# Keg_Cop_-_Tallboy.net
KiCad netlist of a schematic drawn in EAGLE
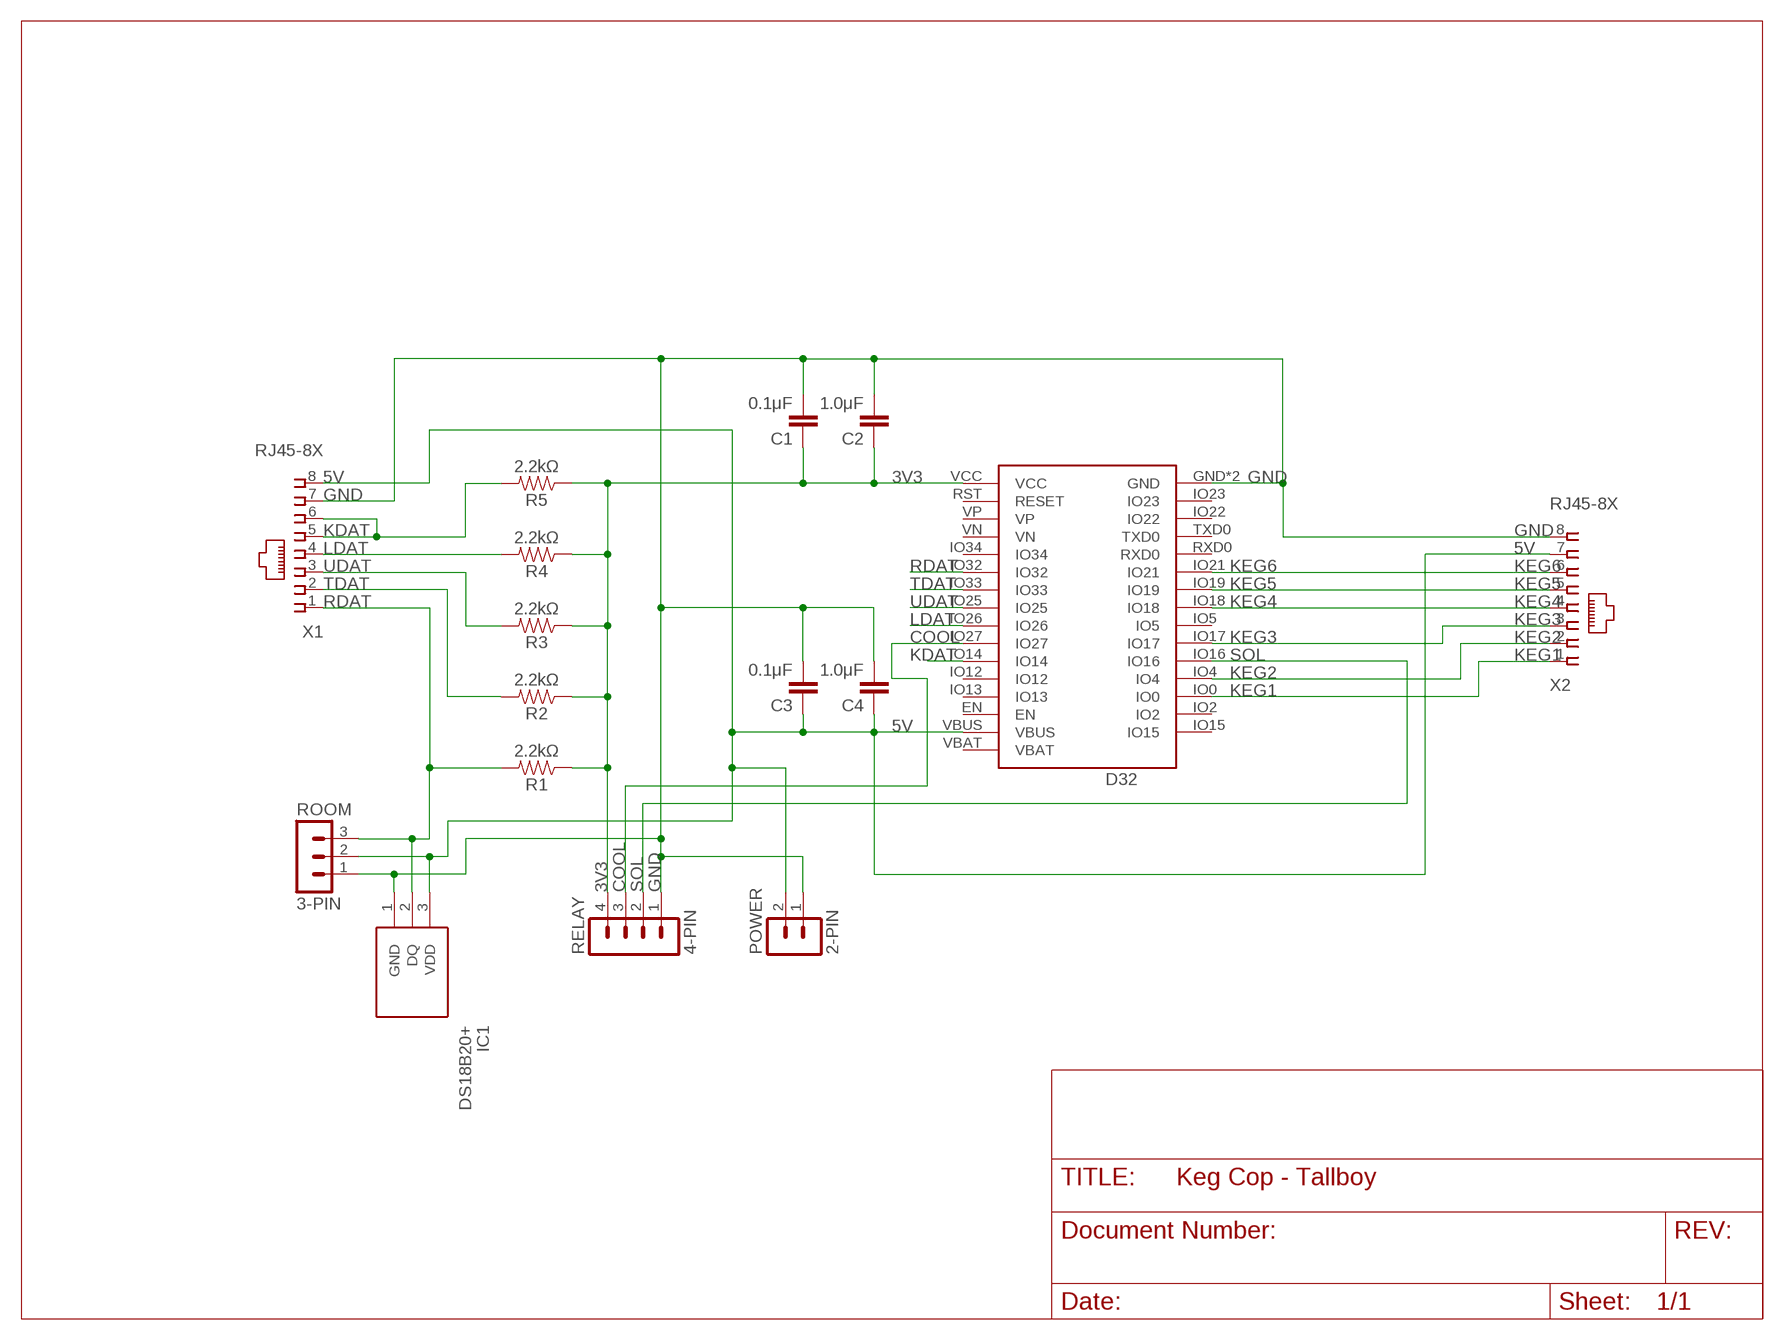
[diagram p0: schematic, sheet 1]

(export (version "E")
  (design (tool "Eeschema 10.0.6"))
  (components
    (comp (ref "C1")
      (value "0.1μF")
      (footprint "eagle-import:CAP_PTH-2.54")
      (libsource (lib "eagle-import") (part "CAP_CERAMIC_2.54"))
    )
    (comp (ref "C2")
      (value "1.0μF")
      (footprint "eagle-import:CAP_PTH-2.54")
      (libsource (lib "eagle-import") (part "CAP_CERAMIC_2.54"))
    )
    (comp (ref "C3")
      (value "0.1μF")
      (footprint "eagle-import:CAP_PTH-2.54")
      (libsource (lib "eagle-import") (part "CAP_CERAMIC_2.54"))
    )
    (comp (ref "C4")
      (value "1.0μF")
      (footprint "eagle-import:CAP_PTH-2.54")
      (libsource (lib "eagle-import") (part "CAP_CERAMIC_2.54"))
    )
    (comp (ref "D32")
      (value "Lolin D32")
      (footprint "eagle-import:D32_NO_BATT")
      (libsource (lib "eagle-import") (part "WEMOS-D32D32_NO_BATT"))
    )
    (comp (ref "IC1")
      (value "DS18B20+")
      (footprint "eagle-import:TO-92")
      (fields (field (name "MOUSER_PART_NUMBER") "700-DS18B20+"))
      (libsource (lib "eagle-import") (part "DS18B20+"))
    )
    (comp (ref "POWER")
      (value "2-PIN")
      (footprint "eagle-import:HDR-2_VERT")
      (libsource (lib "eagle-import") (part "HDR-2"))
    )
    (comp (ref "R1")
      (value "2.2kΩ")
      (footprint "eagle-import:AXIAL-0.3")
      (libsource (lib "eagle-import") (part "RESISTORAXIAL-0.3"))
    )
    (comp (ref "R2")
      (value "2.2kΩ")
      (footprint "eagle-import:AXIAL-0.3")
      (libsource (lib "eagle-import") (part "RESISTORAXIAL-0.3"))
    )
    (comp (ref "R3")
      (value "2.2kΩ")
      (footprint "eagle-import:AXIAL-0.3")
      (libsource (lib "eagle-import") (part "RESISTORAXIAL-0.3"))
    )
    (comp (ref "R4")
      (value "2.2kΩ")
      (footprint "eagle-import:AXIAL-0.3")
      (libsource (lib "eagle-import") (part "RESISTORAXIAL-0.3"))
    )
    (comp (ref "R5")
      (value "2.2kΩ")
      (footprint "eagle-import:AXIAL-0.3")
      (libsource (lib "eagle-import") (part "RESISTORAXIAL-0.3"))
    )
    (comp (ref "RELAY")
      (value "4-PIN")
      (footprint "eagle-import:MA04-1")
      (libsource (lib "eagle-import") (part "MA04-1"))
    )
    (comp (ref "ROOM")
      (value "3-PIN")
      (footprint "eagle-import:HDR-3_VERT")
      (libsource (lib "eagle-import") (part "HDR-3"))
    )
    (comp (ref "X1")
      (value "RJ45-8X")
      (footprint "eagle-import:RJ45-NO-SHIELD")
      (libsource (lib "eagle-import") (part "RJ45-8X"))
    )
    (comp (ref "X2")
      (value "RJ45-8X")
      (footprint "eagle-import:RJ45-NO-SHIELD")
      (libsource (lib "eagle-import") (part "RJ45-8X"))
    )
  )
  (nets
    (net (code "1") (name "/3V3") (class "Default")
      (node (ref "C1") (pin "1") (pinfunction "1_1") (pintype "passive"))
      (node (ref "C2") (pin "1") (pinfunction "1_1") (pintype "passive"))
      (node (ref "D32") (pin "VCC") (pinfunction "VCC_VCC") (pintype "power_in"))
      (node (ref "R1") (pin "P$1") (pinfunction "1_P$1") (pintype "passive"))
      (node (ref "R2") (pin "P$1") (pinfunction "1_P$1") (pintype "passive"))
      (node (ref "R3") (pin "P$1") (pinfunction "1_P$1") (pintype "passive"))
      (node (ref "R4") (pin "P$1") (pinfunction "1_P$1") (pintype "passive"))
      (node (ref "R5") (pin "P$1") (pinfunction "1_P$1") (pintype "passive"))
      (node (ref "RELAY") (pin "4") (pinfunction "4_4") (pintype "passive"))
    )
    (net (code "2") (name "/5V") (class "Default")
      (node (ref "C3") (pin "1") (pinfunction "1_1") (pintype "passive"))
      (node (ref "C4") (pin "1") (pinfunction "1_1") (pintype "passive"))
      (node (ref "D32") (pin "VBUS") (pinfunction "VBUS_VBUS") (pintype "bidirectional"))
      (node (ref "IC1") (pin "3") (pinfunction "VDD_3") (pintype "power_in"))
      (node (ref "POWER") (pin "2") (pinfunction "2_2") (pintype "passive"))
      (node (ref "ROOM") (pin "2") (pinfunction "2_2") (pintype "passive"))
      (node (ref "X1") (pin "8") (pinfunction "8_8") (pintype "passive"))
      (node (ref "X2") (pin "7") (pinfunction "7_7") (pintype "passive"))
    )
    (net (code "3") (name "/COOL") (class "Default")
      (node (ref "D32") (pin "IO27") (pinfunction "IO27_IO27") (pintype "bidirectional"))
      (node (ref "RELAY") (pin "3") (pinfunction "3_3") (pintype "passive"))
    )
    (net (code "4") (name "/GND") (class "Default")
      (node (ref "C1") (pin "2") (pinfunction "2_2") (pintype "passive"))
      (node (ref "C2") (pin "2") (pinfunction "2_2") (pintype "passive"))
      (node (ref "C3") (pin "2") (pinfunction "2_2") (pintype "passive"))
      (node (ref "C4") (pin "2") (pinfunction "2_2") (pintype "passive"))
      (node (ref "D32") (pin "GND") (pinfunction "GND_GND") (pintype "power_in"))
      (node (ref "D32") (pin "GND2") (pinfunction "GND_GND2") (pintype "power_in"))
      (node (ref "IC1") (pin "1") (pinfunction "GND_1") (pintype "power_in"))
      (node (ref "POWER") (pin "1") (pinfunction "1_1") (pintype "passive"))
      (node (ref "RELAY") (pin "1") (pinfunction "1_1") (pintype "passive"))
      (node (ref "ROOM") (pin "1") (pinfunction "1_1") (pintype "passive"))
      (node (ref "X1") (pin "7") (pinfunction "7_7") (pintype "passive"))
      (node (ref "X2") (pin "8") (pinfunction "8_8") (pintype "passive"))
    )
    (net (code "5") (name "/KDAT") (class "Default")
      (node (ref "D32") (pin "IO14") (pinfunction "IO14_IO14") (pintype "bidirectional"))
      (node (ref "R5") (pin "P$2") (pinfunction "2_P$2") (pintype "passive"))
      (node (ref "X1") (pin "5") (pinfunction "5_5") (pintype "passive"))
      (node (ref "X1") (pin "6") (pinfunction "6_6") (pintype "passive"))
    )
    (net (code "6") (name "/KEG1") (class "Default")
      (node (ref "D32") (pin "IO0") (pinfunction "IO0_IO0") (pintype "bidirectional"))
      (node (ref "X2") (pin "1") (pinfunction "1_1") (pintype "passive"))
    )
    (net (code "7") (name "/KEG2") (class "Default")
      (node (ref "D32") (pin "IO4") (pinfunction "IO4_IO4") (pintype "bidirectional"))
      (node (ref "X2") (pin "2") (pinfunction "2_2") (pintype "passive"))
    )
    (net (code "8") (name "/KEG3") (class "Default")
      (node (ref "D32") (pin "IO17") (pinfunction "IO17_IO17") (pintype "bidirectional"))
      (node (ref "X2") (pin "3") (pinfunction "3_3") (pintype "passive"))
    )
    (net (code "9") (name "/KEG4") (class "Default")
      (node (ref "D32") (pin "IO18") (pinfunction "IO18_IO18") (pintype "bidirectional"))
      (node (ref "X2") (pin "4") (pinfunction "4_4") (pintype "passive"))
    )
    (net (code "10") (name "/KEG5") (class "Default")
      (node (ref "D32") (pin "IO19") (pinfunction "IO19_IO19") (pintype "bidirectional"))
      (node (ref "X2") (pin "5") (pinfunction "5_5") (pintype "passive"))
    )
    (net (code "11") (name "/KEG6") (class "Default")
      (node (ref "D32") (pin "IO21") (pinfunction "IO21_IO21") (pintype "bidirectional"))
      (node (ref "X2") (pin "6") (pinfunction "6_6") (pintype "passive"))
    )
    (net (code "12") (name "/LDAT") (class "Default")
      (node (ref "D32") (pin "IO26") (pinfunction "IO26_IO26") (pintype "bidirectional"))
      (node (ref "R4") (pin "P$2") (pinfunction "2_P$2") (pintype "passive"))
      (node (ref "X1") (pin "4") (pinfunction "4_4") (pintype "passive"))
    )
    (net (code "13") (name "/RDAT") (class "Default")
      (node (ref "D32") (pin "IO32") (pinfunction "IO32_IO32") (pintype "bidirectional"))
      (node (ref "IC1") (pin "2") (pinfunction "DQ_2") (pintype "bidirectional"))
      (node (ref "R1") (pin "P$2") (pinfunction "2_P$2") (pintype "passive"))
      (node (ref "ROOM") (pin "3") (pinfunction "3_3") (pintype "passive"))
      (node (ref "X1") (pin "1") (pinfunction "1_1") (pintype "passive"))
    )
    (net (code "14") (name "/SOL") (class "Default")
      (node (ref "D32") (pin "IO16") (pinfunction "IO16_IO16") (pintype "bidirectional"))
      (node (ref "RELAY") (pin "2") (pinfunction "2_2") (pintype "passive"))
    )
    (net (code "15") (name "/TDAT") (class "Default")
      (node (ref "D32") (pin "IO33") (pinfunction "IO33_IO33") (pintype "bidirectional"))
      (node (ref "R2") (pin "P$2") (pinfunction "2_P$2") (pintype "passive"))
      (node (ref "X1") (pin "2") (pinfunction "2_2") (pintype "passive"))
    )
    (net (code "16") (name "/UDAT") (class "Default")
      (node (ref "D32") (pin "IO25") (pinfunction "IO25_IO25") (pintype "bidirectional"))
      (node (ref "R3") (pin "P$2") (pinfunction "2_P$2") (pintype "passive"))
      (node (ref "X1") (pin "3") (pinfunction "3_3") (pintype "passive"))
    )
    (net (code "17") (name "unconnected-(D32-PadEN)") (class "Default")
      (node (ref "D32") (pin "EN") (pinfunction "EN_EN") (pintype "bidirectional"))
    )
    (net (code "18") (name "unconnected-(D32-PadIO2)") (class "Default")
      (node (ref "D32") (pin "IO2") (pinfunction "IO2_IO2") (pintype "bidirectional"))
    )
    (net (code "19") (name "unconnected-(D32-PadIO5)") (class "Default")
      (node (ref "D32") (pin "IO5") (pinfunction "IO5_IO5") (pintype "bidirectional"))
    )
    (net (code "20") (name "unconnected-(D32-PadIO12)") (class "Default")
      (node (ref "D32") (pin "IO12") (pinfunction "IO12_IO12") (pintype "bidirectional"))
    )
    (net (code "21") (name "unconnected-(D32-PadIO13)") (class "Default")
      (node (ref "D32") (pin "IO13") (pinfunction "IO13_IO13") (pintype "bidirectional"))
    )
    (net (code "22") (name "unconnected-(D32-PadIO15)") (class "Default")
      (node (ref "D32") (pin "IO15") (pinfunction "IO15_IO15") (pintype "bidirectional"))
    )
    (net (code "23") (name "unconnected-(D32-PadIO22)") (class "Default")
      (node (ref "D32") (pin "IO22") (pinfunction "IO22_IO22") (pintype "bidirectional"))
    )
    (net (code "24") (name "unconnected-(D32-PadIO23)") (class "Default")
      (node (ref "D32") (pin "IO23") (pinfunction "IO23_IO23") (pintype "bidirectional"))
    )
    (net (code "25") (name "unconnected-(D32-PadIO34)") (class "Default")
      (node (ref "D32") (pin "IO34") (pinfunction "IO34_IO34") (pintype "bidirectional"))
    )
    (net (code "26") (name "unconnected-(D32-PadRXD0)") (class "Default")
      (node (ref "D32") (pin "RXD0") (pinfunction "RXD0_RXD0") (pintype "input"))
    )
    (net (code "27") (name "unconnected-(D32-PadTXD0)") (class "Default")
      (node (ref "D32") (pin "TXD0") (pinfunction "TXD0_TXD0") (pintype "output"))
    )
    (net (code "28") (name "unconnected-(D32-PadVBAT)") (class "Default")
      (node (ref "D32") (pin "VBAT") (pinfunction "VBAT_VBAT") (pintype "bidirectional"))
    )
    (net (code "29") (name "unconnected-(D32-PadVN)") (class "Default")
      (node (ref "D32") (pin "VN") (pinfunction "VN_VN") (pintype "bidirectional"))
    )
    (net (code "30") (name "unconnected-(D32-PadVP)") (class "Default")
      (node (ref "D32") (pin "VP") (pinfunction "VP_VP") (pintype "bidirectional"))
    )
    (net (code "31") (name "unconnected-(D32-RESET-PadRST)") (class "Default")
      (node (ref "D32") (pin "RST") (pinfunction "RESET_RST") (pintype "bidirectional"))
    )
  )
)
